# voice.net
KiCad netlist of a schematic drawn in Altium Designer
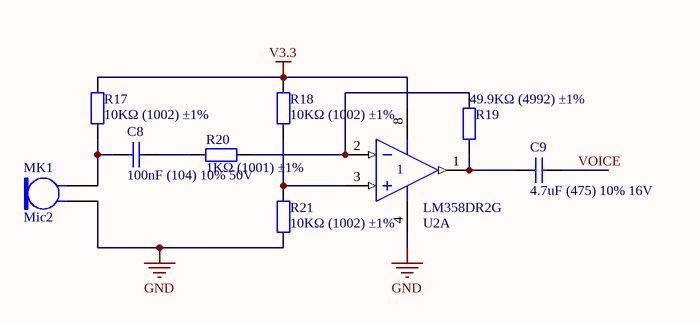
[diagram p0: voice.SchDoc]

(export (version "E")
  (design (tool "Eeschema 10.0.6"))
  (components
    (comp (ref "C8")
      (value "100nF (104) 10% 50V")
      (footprint "0603_C")
      (description "贴片电容")
      (libsource (lib "Miscellaneous Devices LC") (part "0603 100nF (104) 10% 50V"))
    )
    (comp (ref "C9")
      (value "4.7uF (475) 10% 16V")
      (footprint "0603_C")
      (description "贴片电容")
      (libsource (lib "Miscellaneous Devices LC") (part "0603 4.7uF (475) 10% 16V"))
    )
    (comp (ref "MK1")
      (value "Mic2")
      (footprint "PIN2")
      (description "Microphone")
      (fields (field (name "PUBLISHER") "Altium Limited"))
      (libsource (lib "Miscellaneous Devices") (part "Mic2"))
    )
    (comp (ref "R17")
      (value "10KΩ (1002) ±1%")
      (footprint "0603_R")
      (description "贴片电阻")
      (libsource (lib "Miscellaneous Devices LC") (part "0603 10KΩ (1002) 1%"))
    )
    (comp (ref "R18")
      (value "10KΩ (1002) ±1%")
      (footprint "0603_R")
      (description "贴片电阻")
      (libsource (lib "Miscellaneous Devices LC") (part "0603 10KΩ (1002) 1%"))
    )
    (comp (ref "R19")
      (value "49.9KΩ (4992) ±1%")
      (footprint "0603_R")
      (description "贴片电阻")
      (libsource (lib "Miscellaneous Devices LC") (part "0603 49.9KΩ (4992) 1%"))
    )
    (comp (ref "R20")
      (value "1KΩ (1001) ±1%")
      (footprint "0603_R")
      (description "贴片电阻")
      (libsource (lib "Miscellaneous Devices LC") (part "0603 1KΩ (1001) 1%"))
    )
    (comp (ref "R21")
      (value "10KΩ (1002) ±1%")
      (footprint "0603_R")
      (description "贴片电阻")
      (libsource (lib "Miscellaneous Devices LC") (part "0603 10KΩ (1002) 1%"))
    )
    (comp (ref "U2")
      (value "LM358DR2G")
      (footprint "SOIC-8_150mil")
      (description "通用运放")
      (libsource (lib "Miscellaneous Devices LC") (part "LM358DR2G_[C7950]"))
    )
  )
  (nets
    (net (code "1") (name "/VOICE") (class "Default")
      (node (ref "C9") (pin "2") (pinfunction "2_2") (pintype "passive"))
    )
    (net (code "2") (name "GND") (class "Default")
      (node (ref "MK1") (pin "1") (pinfunction "1_1") (pintype "passive"))
      (node (ref "R21") (pin "1") (pinfunction "1_1") (pintype "passive"))
      (node (ref "U2") (pin "4") (pinfunction "V-_4") (pintype "power_in"))
    )
    (net (code "3") (name "Net-(C8-Pad1)") (class "Default")
      (node (ref "C8") (pin "1") (pinfunction "1_1") (pintype "passive"))
      (node (ref "MK1") (pin "2") (pinfunction "2_2") (pintype "passive"))
      (node (ref "R17") (pin "1") (pinfunction "1_1") (pintype "passive"))
    )
    (net (code "4") (name "Net-(C8-Pad2)") (class "Default")
      (node (ref "C8") (pin "2") (pinfunction "2_2") (pintype "passive"))
      (node (ref "R20") (pin "1") (pinfunction "1_1") (pintype "passive"))
    )
    (net (code "5") (name "Net-(U2A-IN+)") (class "Default")
      (node (ref "R18") (pin "1") (pinfunction "1_1") (pintype "passive"))
      (node (ref "R21") (pin "2") (pinfunction "2_2") (pintype "passive"))
      (node (ref "U2") (pin "3") (pinfunction "IN+_3") (pintype "input"))
    )
    (net (code "6") (name "Net-(U2A-IN-)") (class "Default")
      (node (ref "R19") (pin "2") (pinfunction "2_2") (pintype "passive"))
      (node (ref "R20") (pin "2") (pinfunction "2_2") (pintype "passive"))
      (node (ref "U2") (pin "2") (pinfunction "IN-_2") (pintype "input"))
    )
    (net (code "7") (name "Net-(U2A-OUT)") (class "Default")
      (node (ref "C9") (pin "1") (pinfunction "1_1") (pintype "passive"))
      (node (ref "R19") (pin "1") (pinfunction "1_1") (pintype "passive"))
      (node (ref "U2") (pin "1") (pinfunction "OUT_1") (pintype "output"))
    )
    (net (code "8") (name "V3.3") (class "Default")
      (node (ref "R17") (pin "2") (pinfunction "2_2") (pintype "passive"))
      (node (ref "R18") (pin "2") (pinfunction "2_2") (pintype "passive"))
      (node (ref "U2") (pin "8") (pinfunction "V+_8") (pintype "power_in"))
    )
  )
)
